# JTAG_Configuration.net
KiCad netlist of a schematic drawn in Altium Designer
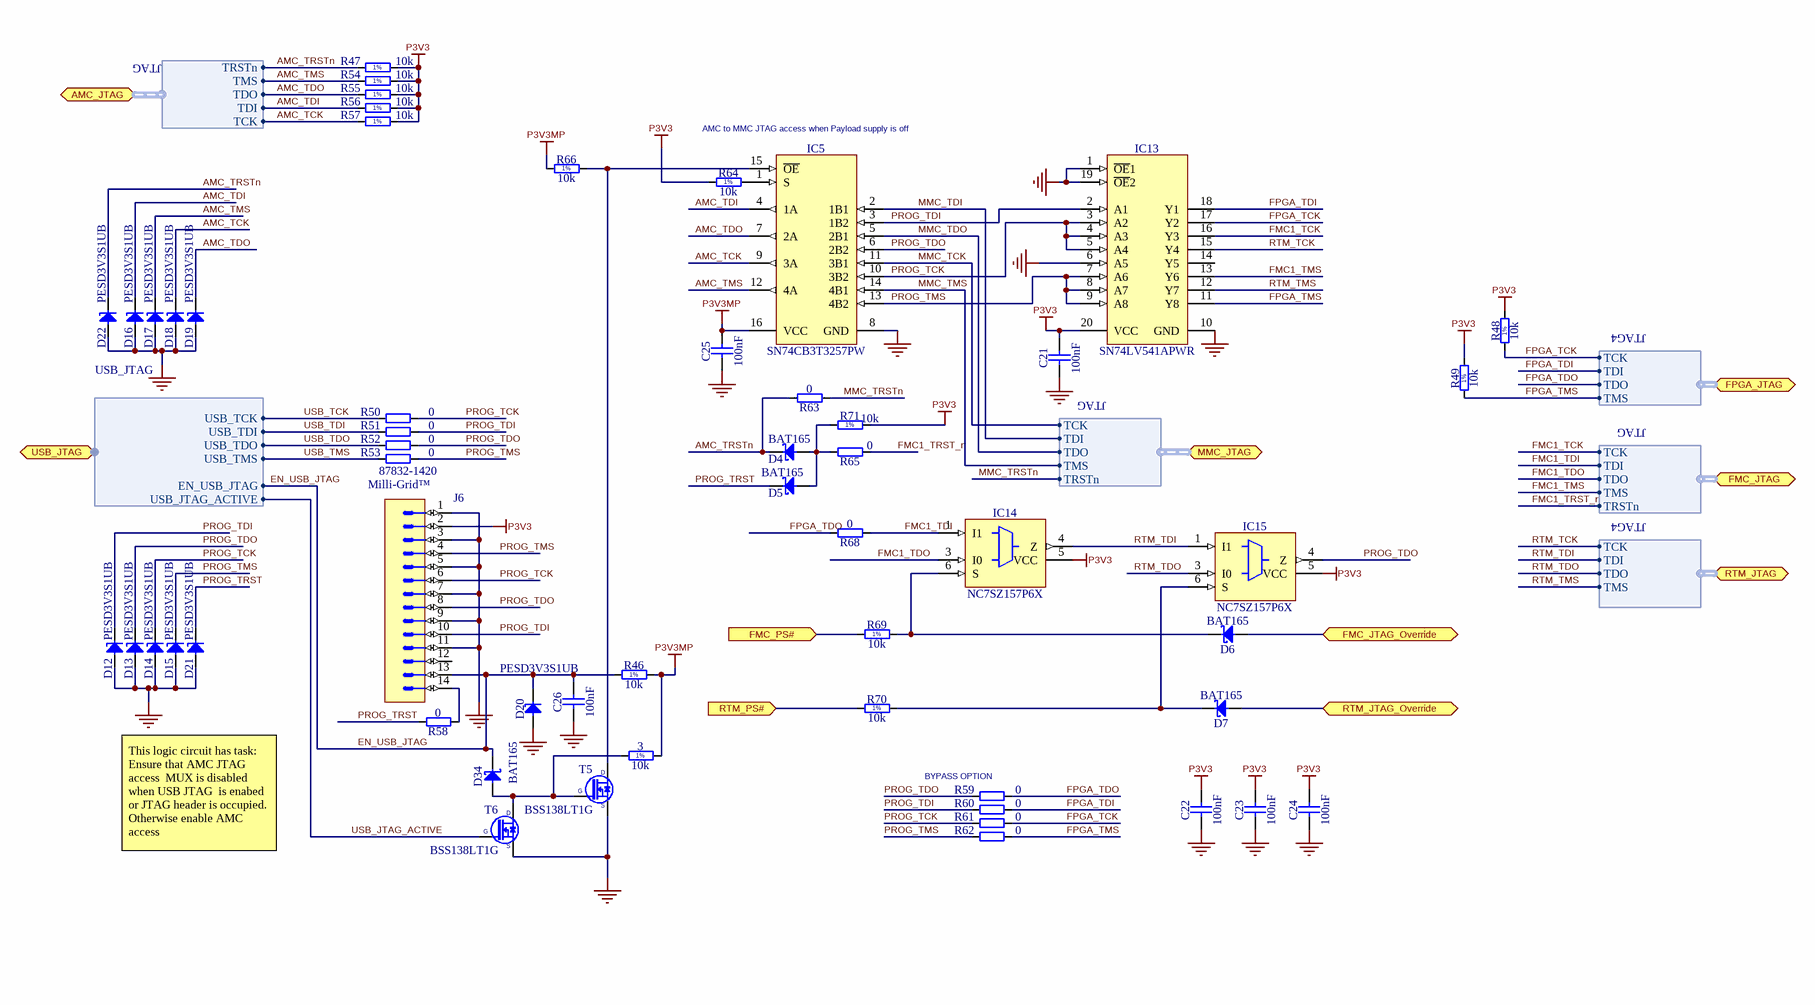
[diagram p0: JTAG_Configuration.SchDoc]

(export (version "E")
  (design (tool "Eeschema 10.0.6"))
  (components
    (comp (ref "3")
      (value "10k")
      (footprint "RESC1005X40N")
      (description "Resistor - 1%")
      (fields
        (field (name "MANUFACTURER PART NUMBER") "R0402_10K_1%_0.0625W_100PPM")
        (field (name "MANUFACTURER") "GENERIC")
        (field (name "AUTHOR") "CERN DEM JLC")
      )
      (libsource (lib "Resistors") (part "Resistor - 1%"))
    )
    (comp (ref "C21")
      (value "100nF")
      (footprint "CAPC0603X33N")
      (description "Non-polarised capacitor")
      (fields
        (field (name "MANUFACTURER PART NUMBER") "CC0201_100NF_6.3V_10%_X5R")
        (field (name "MANUFACTURER") "GENERIC")
        (field (name "AUTHOR") "CERN DEM JLC")
      )
      (libsource (lib "Capacitors") (part "Capacitor - non polarized"))
    )
    (comp (ref "C22")
      (value "100nF")
      (footprint "CAPC0603X33N")
      (description "Non-polarised capacitor")
      (fields
        (field (name "MANUFACTURER PART NUMBER") "CC0201_100NF_6.3V_10%_X5R")
        (field (name "MANUFACTURER") "GENERIC")
        (field (name "AUTHOR") "CERN DEM JLC")
      )
      (libsource (lib "Capacitors") (part "Capacitor - non polarized"))
    )
    (comp (ref "C23")
      (value "100nF")
      (footprint "CAPC0603X33N")
      (description "Non-polarised capacitor")
      (fields
        (field (name "MANUFACTURER PART NUMBER") "CC0201_100NF_6.3V_10%_X5R")
        (field (name "MANUFACTURER") "GENERIC")
        (field (name "AUTHOR") "CERN DEM JLC")
      )
      (libsource (lib "Capacitors") (part "Capacitor - non polarized"))
    )
    (comp (ref "C24")
      (value "100nF")
      (footprint "CAPC0603X33N")
      (description "Non-polarised capacitor")
      (fields
        (field (name "MANUFACTURER PART NUMBER") "CC0201_100NF_6.3V_10%_X5R")
        (field (name "MANUFACTURER") "GENERIC")
        (field (name "AUTHOR") "CERN DEM JLC")
      )
      (libsource (lib "Capacitors") (part "Capacitor - non polarized"))
    )
    (comp (ref "C25")
      (value "100nF")
      (footprint "CAPC0603X33N")
      (description "Non-polarised capacitor")
      (fields
        (field (name "MANUFACTURER PART NUMBER") "CC0201_100NF_6.3V_10%_X5R")
        (field (name "MANUFACTURER") "GENERIC")
        (field (name "AUTHOR") "CERN DEM JLC")
      )
      (libsource (lib "Capacitors") (part "Capacitor - non polarized"))
    )
    (comp (ref "C26")
      (value "100nF")
      (footprint "CAPC0603X33N")
      (description "Non-polarised capacitor")
      (fields
        (field (name "MANUFACTURER PART NUMBER") "CC0201_100NF_6.3V_10%_X5R")
        (field (name "MANUFACTURER") "GENERIC")
        (field (name "AUTHOR") "CERN DEM JLC")
      )
      (libsource (lib "Capacitors") (part "Capacitor - non polarized"))
    )
    (comp (ref "D4")
      (value "BAT165")
      (footprint "SOD2512X110N")
      (description "Schottky Diode")
      (fields
        (field (name "MANUFACTURER") "INFINEON")
        (field (name "VOLTAGE") "40V")
        (field (name "AUTHOR") "CERN DEM JLC")
      )
      (libsource (lib "ICs And Semiconductors") (part "Diode Schottky"))
    )
    (comp (ref "D5")
      (value "BAT165")
      (footprint "SOD2512X110N")
      (description "Schottky Diode")
      (fields
        (field (name "MANUFACTURER") "INFINEON")
        (field (name "VOLTAGE") "40V")
        (field (name "AUTHOR") "CERN DEM JLC")
      )
      (libsource (lib "ICs And Semiconductors") (part "Diode Schottky"))
    )
    (comp (ref "D6")
      (value "BAT165")
      (footprint "SOD2512X110N")
      (description "Schottky Diode")
      (fields
        (field (name "MANUFACTURER") "INFINEON")
        (field (name "VOLTAGE") "40V")
        (field (name "AUTHOR") "CERN DEM JLC")
      )
      (libsource (lib "ICs And Semiconductors") (part "Diode Schottky"))
    )
    (comp (ref "D7")
      (value "BAT165")
      (footprint "SOD2512X110N")
      (description "Schottky Diode")
      (fields
        (field (name "MANUFACTURER") "INFINEON")
        (field (name "VOLTAGE") "40V")
        (field (name "AUTHOR") "CERN DEM JLC")
      )
      (libsource (lib "ICs And Semiconductors") (part "Diode Schottky"))
    )
    (comp (ref "D12")
      (value "PESD3V3S1UB")
      (footprint "SODFL1608X65N")
      (description "ESD protection diode")
      (fields
        (field (name "MANUFACTURER") "NXP SEMICONDUCTORS")
        (field (name "VOLTAGE") "3V3")
        (field (name "AUTHOR") "CERN DEM JLC")
      )
      (libsource (lib "ICs And Semiconductors") (part "Diode ESD"))
    )
    (comp (ref "D13")
      (value "PESD3V3S1UB")
      (footprint "SODFL1608X65N")
      (description "ESD protection diode")
      (fields
        (field (name "MANUFACTURER") "NXP SEMICONDUCTORS")
        (field (name "VOLTAGE") "3V3")
        (field (name "AUTHOR") "CERN DEM JLC")
      )
      (libsource (lib "ICs And Semiconductors") (part "Diode ESD"))
    )
    (comp (ref "D14")
      (value "PESD3V3S1UB")
      (footprint "SODFL1608X65N")
      (description "ESD protection diode")
      (fields
        (field (name "MANUFACTURER") "NXP SEMICONDUCTORS")
        (field (name "VOLTAGE") "3V3")
        (field (name "AUTHOR") "CERN DEM JLC")
      )
      (libsource (lib "ICs And Semiconductors") (part "Diode ESD"))
    )
    (comp (ref "D15")
      (value "PESD3V3S1UB")
      (footprint "SODFL1608X65N")
      (description "ESD protection diode")
      (fields
        (field (name "MANUFACTURER") "NXP SEMICONDUCTORS")
        (field (name "VOLTAGE") "3V3")
        (field (name "AUTHOR") "CERN DEM JLC")
      )
      (libsource (lib "ICs And Semiconductors") (part "Diode ESD"))
    )
    (comp (ref "D16")
      (value "PESD3V3S1UB")
      (footprint "SODFL1608X65N")
      (description "ESD protection diode")
      (fields
        (field (name "MANUFACTURER") "NXP SEMICONDUCTORS")
        (field (name "VOLTAGE") "3V3")
        (field (name "AUTHOR") "CERN DEM JLC")
      )
      (libsource (lib "ICs And Semiconductors") (part "Diode ESD"))
    )
    (comp (ref "D17")
      (value "PESD3V3S1UB")
      (footprint "SODFL1608X65N")
      (description "ESD protection diode")
      (fields
        (field (name "MANUFACTURER") "NXP SEMICONDUCTORS")
        (field (name "VOLTAGE") "3V3")
        (field (name "AUTHOR") "CERN DEM JLC")
      )
      (libsource (lib "ICs And Semiconductors") (part "Diode ESD"))
    )
    (comp (ref "D18")
      (value "PESD3V3S1UB")
      (footprint "SODFL1608X65N")
      (description "ESD protection diode")
      (fields
        (field (name "MANUFACTURER") "NXP SEMICONDUCTORS")
        (field (name "VOLTAGE") "3V3")
        (field (name "AUTHOR") "CERN DEM JLC")
      )
      (libsource (lib "ICs And Semiconductors") (part "Diode ESD"))
    )
    (comp (ref "D19")
      (value "PESD3V3S1UB")
      (footprint "SODFL1608X65N")
      (description "ESD protection diode")
      (fields
        (field (name "MANUFACTURER") "NXP SEMICONDUCTORS")
        (field (name "VOLTAGE") "3V3")
        (field (name "AUTHOR") "CERN DEM JLC")
      )
      (libsource (lib "ICs And Semiconductors") (part "Diode ESD"))
    )
    (comp (ref "D20")
      (value "PESD3V3S1UB")
      (footprint "SODFL1608X65N")
      (description "ESD protection diode")
      (fields
        (field (name "MANUFACTURER") "NXP SEMICONDUCTORS")
        (field (name "VOLTAGE") "3V3")
        (field (name "AUTHOR") "CERN DEM JLC")
      )
      (libsource (lib "ICs And Semiconductors") (part "Diode ESD"))
    )
    (comp (ref "D21")
      (value "PESD3V3S1UB")
      (footprint "SODFL1608X65N")
      (description "ESD protection diode")
      (fields
        (field (name "MANUFACTURER") "NXP SEMICONDUCTORS")
        (field (name "VOLTAGE") "3V3")
        (field (name "AUTHOR") "CERN DEM JLC")
      )
      (libsource (lib "ICs And Semiconductors") (part "Diode ESD"))
    )
    (comp (ref "D22")
      (value "PESD3V3S1UB")
      (footprint "SODFL1608X65N")
      (description "ESD protection diode")
      (fields
        (field (name "MANUFACTURER") "NXP SEMICONDUCTORS")
        (field (name "VOLTAGE") "3V3")
        (field (name "AUTHOR") "CERN DEM JLC")
      )
      (libsource (lib "ICs And Semiconductors") (part "Diode ESD"))
    )
    (comp (ref "D34")
      (value "BAT165")
      (footprint "SOD2512X110N")
      (description "Schottky Diode")
      (fields
        (field (name "MANUFACTURER") "INFINEON")
        (field (name "VOLTAGE") "40V")
        (field (name "AUTHOR") "CERN DEM JLC")
      )
      (libsource (lib "ICs And Semiconductors") (part "Diode Schottky"))
    )
    (comp (ref "IC5")
      (value "SN74CB3T3257PW")
      (footprint "SOP65P640X120-16N")
      (description "4-BIT 1-OF-2 FET Multiplexer/Demultiplexer 2.5V/3.3V Low-Voltage Bus Switch 5V Tolerant Shifter")
      (fields (field (name "MANUFACTURER") "TEXAS INSTRUMENTS") (field (name "AUTHOR") "CERN DEM JLC"))
      (libsource (lib "ICs And Semiconductors") (part "743257"))
    )
    (comp (ref "IC13")
      (value "SN74LV541APWR")
      (footprint "SOP65P640X120-20N")
      (description "Octal Buffer/Line Driver with 3-State Outputs")
      (fields (field (name "MANUFACTURER") "TEXAS INSTRUMENTS") (field (name "AUTHOR") "CERN DEM JLC"))
      (libsource (lib "ICs And Semiconductors") (part "74541"))
    )
    (comp (ref "IC14")
      (value "NC7SZ157P6X")
      (footprint "SOT65P210X110-6N")
      (description "TinyLogic® UHS 2-Input Non-Inverting Multiplexer")
      (fields (field (name "MANUFACTURER") "FAIRCHILD SEMICONDUCTOR") (field (name "AUTHOR") "CERN DEM JLC"))
      (libsource (lib "ICs And Semiconductors") (part "NC7SZ157"))
    )
    (comp (ref "IC15")
      (value "NC7SZ157P6X")
      (footprint "SOT65P210X110-6N")
      (description "TinyLogic® UHS 2-Input Non-Inverting Multiplexer")
      (fields (field (name "MANUFACTURER") "FAIRCHILD SEMICONDUCTOR") (field (name "AUTHOR") "CERN DEM JLC"))
      (libsource (lib "ICs And Semiconductors") (part "NC7SZ157"))
    )
    (comp (ref "J6")
      (value "Milli-Grid™")
      (footprint "MOLEX_87832-1420")
      (description "Connector 14 Male")
      (fields
        (field (name "MANUFACTURER PART NUMBER") "87832-1420")
        (field (name "MANUFACTURER") "MOLEX")
        (field (name "PART NUMBER") "MOLEX_87832-1420")
        (field (name "AUTHOR") "CERN DEM JLC")
      )
      (libsource (lib "Connectors") (part "Connector 14 Male"))
    )
    (comp (ref "R46")
      (value "10k")
      (footprint "RESC1005X40N")
      (description "Resistor - 1%")
      (fields
        (field (name "MANUFACTURER PART NUMBER") "R0402_10K_1%_0.0625W_100PPM")
        (field (name "MANUFACTURER") "GENERIC")
        (field (name "AUTHOR") "CERN DEM JLC")
      )
      (libsource (lib "Resistors") (part "Resistor - 1%"))
    )
    (comp (ref "R47")
      (value "10k")
      (footprint "RESC1005X40N")
      (description "Resistor - 1%")
      (fields
        (field (name "MANUFACTURER PART NUMBER") "R0402_10K_1%_0.0625W_100PPM")
        (field (name "MANUFACTURER") "GENERIC")
        (field (name "AUTHOR") "CERN DEM JLC")
      )
      (libsource (lib "Resistors") (part "Resistor - 1%"))
    )
    (comp (ref "R48")
      (value "10k")
      (footprint "RESC1005X40N")
      (description "Resistor - 1%")
      (fields
        (field (name "MANUFACTURER PART NUMBER") "R0402_10K_1%_0.0625W_100PPM")
        (field (name "MANUFACTURER") "GENERIC")
        (field (name "AUTHOR") "CERN DEM JLC")
      )
      (libsource (lib "Resistors") (part "Resistor - 1%"))
    )
    (comp (ref "R49")
      (value "10k")
      (footprint "RESC1005X40N")
      (description "Resistor - 1%")
      (fields
        (field (name "MANUFACTURER PART NUMBER") "R0402_10K_1%_0.0625W_100PPM")
        (field (name "MANUFACTURER") "GENERIC")
        (field (name "AUTHOR") "CERN DEM JLC")
      )
      (libsource (lib "Resistors") (part "Resistor - 1%"))
    )
    (comp (ref "R50")
      (value "0")
      (footprint "RESC1005X40N")
      (description "Resistor")
      (fields
        (field (name "MANUFACTURER PART NUMBER") "R0402_0R_JUMPER")
        (field (name "MANUFACTURER") "GENERIC")
        (field (name "AUTHOR") "CERN DEM JLC")
      )
      (libsource (lib "Resistors") (part "Resistor"))
    )
    (comp (ref "R51")
      (value "0")
      (footprint "RESC1005X40N")
      (description "Resistor")
      (fields
        (field (name "MANUFACTURER PART NUMBER") "R0402_0R_JUMPER")
        (field (name "MANUFACTURER") "GENERIC")
        (field (name "AUTHOR") "CERN DEM JLC")
      )
      (libsource (lib "Resistors") (part "Resistor"))
    )
    (comp (ref "R52")
      (value "0")
      (footprint "RESC1005X40N")
      (description "Resistor")
      (fields
        (field (name "MANUFACTURER PART NUMBER") "R0402_0R_JUMPER")
        (field (name "MANUFACTURER") "GENERIC")
        (field (name "AUTHOR") "CERN DEM JLC")
      )
      (libsource (lib "Resistors") (part "Resistor"))
    )
    (comp (ref "R53")
      (value "0")
      (footprint "RESC1005X40N")
      (description "Resistor")
      (fields
        (field (name "MANUFACTURER PART NUMBER") "R0402_0R_JUMPER")
        (field (name "MANUFACTURER") "GENERIC")
        (field (name "AUTHOR") "CERN DEM JLC")
      )
      (libsource (lib "Resistors") (part "Resistor"))
    )
    (comp (ref "R54")
      (value "10k")
      (footprint "RESC1005X40N")
      (description "Resistor - 1%")
      (fields
        (field (name "MANUFACTURER PART NUMBER") "R0402_10K_1%_0.0625W_100PPM")
        (field (name "MANUFACTURER") "GENERIC")
        (field (name "AUTHOR") "CERN DEM JLC")
      )
      (libsource (lib "Resistors") (part "Resistor - 1%"))
    )
    (comp (ref "R55")
      (value "10k")
      (footprint "RESC1005X40N")
      (description "Resistor - 1%")
      (fields
        (field (name "MANUFACTURER PART NUMBER") "R0402_10K_1%_0.0625W_100PPM")
        (field (name "MANUFACTURER") "GENERIC")
        (field (name "AUTHOR") "CERN DEM JLC")
      )
      (libsource (lib "Resistors") (part "Resistor - 1%"))
    )
    (comp (ref "R56")
      (value "10k")
      (footprint "RESC1005X40N")
      (description "Resistor - 1%")
      (fields
        (field (name "MANUFACTURER PART NUMBER") "R0402_10K_1%_0.0625W_100PPM")
        (field (name "MANUFACTURER") "GENERIC")
        (field (name "AUTHOR") "CERN DEM JLC")
      )
      (libsource (lib "Resistors") (part "Resistor - 1%"))
    )
    (comp (ref "R57")
      (value "10k")
      (footprint "RESC1005X40N")
      (description "Resistor - 1%")
      (fields
        (field (name "MANUFACTURER PART NUMBER") "R0402_10K_1%_0.0625W_100PPM")
        (field (name "MANUFACTURER") "GENERIC")
        (field (name "AUTHOR") "CERN DEM JLC")
      )
      (libsource (lib "Resistors") (part "Resistor - 1%"))
    )
    (comp (ref "R58")
      (value "0")
      (footprint "RESC1005X40N")
      (description "Resistor")
      (fields
        (field (name "MANUFACTURER PART NUMBER") "R0402_0R_JUMPER")
        (field (name "MANUFACTURER") "GENERIC")
        (field (name "AUTHOR") "CERN DEM JLC")
      )
      (libsource (lib "Resistors") (part "Resistor"))
    )
    (comp (ref "R59")
      (value "0")
      (footprint "RESC1005X40N")
      (description "Resistor")
      (fields
        (field (name "MANUFACTURER PART NUMBER") "R0402_0R_JUMPER")
        (field (name "MANUFACTURER") "GENERIC")
        (field (name "AUTHOR") "CERN DEM JLC")
      )
      (libsource (lib "Resistors") (part "Resistor"))
    )
    (comp (ref "R60")
      (value "0")
      (footprint "RESC1005X40N")
      (description "Resistor")
      (fields
        (field (name "MANUFACTURER PART NUMBER") "R0402_0R_JUMPER")
        (field (name "MANUFACTURER") "GENERIC")
        (field (name "AUTHOR") "CERN DEM JLC")
      )
      (libsource (lib "Resistors") (part "Resistor"))
    )
    (comp (ref "R61")
      (value "0")
      (footprint "RESC1005X40N")
      (description "Resistor")
      (fields
        (field (name "MANUFACTURER PART NUMBER") "R0402_0R_JUMPER")
        (field (name "MANUFACTURER") "GENERIC")
        (field (name "AUTHOR") "CERN DEM JLC")
      )
      (libsource (lib "Resistors") (part "Resistor"))
    )
    (comp (ref "R62")
      (value "0")
      (footprint "RESC1005X40N")
      (description "Resistor")
      (fields
        (field (name "MANUFACTURER PART NUMBER") "R0402_0R_JUMPER")
        (field (name "MANUFACTURER") "GENERIC")
        (field (name "AUTHOR") "CERN DEM JLC")
      )
      (libsource (lib "Resistors") (part "Resistor"))
    )
    (comp (ref "R63")
      (value "0")
      (footprint "RESC1005X40N")
      (description "Resistor")
      (fields
        (field (name "MANUFACTURER PART NUMBER") "R0402_0R_JUMPER")
        (field (name "MANUFACTURER") "GENERIC")
        (field (name "AUTHOR") "CERN DEM JLC")
      )
      (libsource (lib "Resistors") (part "Resistor"))
    )
    (comp (ref "R64")
      (value "10k")
      (footprint "RESC1005X40N")
      (description "Resistor - 1%")
      (fields
        (field (name "MANUFACTURER PART NUMBER") "R0402_10K_1%_0.0625W_100PPM")
        (field (name "MANUFACTURER") "GENERIC")
        (field (name "AUTHOR") "CERN DEM JLC")
      )
      (libsource (lib "Resistors") (part "Resistor - 1%"))
    )
    (comp (ref "R65")
      (value "0")
      (footprint "RESC1005X40N")
      (description "Resistor")
      (fields
        (field (name "MANUFACTURER PART NUMBER") "R0402_0R_JUMPER")
        (field (name "MANUFACTURER") "GENERIC")
        (field (name "AUTHOR") "CERN DEM JLC")
      )
      (libsource (lib "Resistors") (part "Resistor"))
    )
    (comp (ref "R66")
      (value "10k")
      (footprint "RESC1005X40N")
      (description "Resistor - 1%")
      (fields
        (field (name "MANUFACTURER PART NUMBER") "R0402_10K_1%_0.0625W_100PPM")
        (field (name "MANUFACTURER") "GENERIC")
        (field (name "AUTHOR") "CERN DEM JLC")
      )
      (libsource (lib "Resistors") (part "Resistor - 1%"))
    )
    (comp (ref "R68")
      (value "0")
      (footprint "RESC1005X40N")
      (description "Resistor")
      (fields
        (field (name "MANUFACTURER PART NUMBER") "R0402_0R_JUMPER")
        (field (name "MANUFACTURER") "GENERIC")
        (field (name "AUTHOR") "CERN DEM JLC")
      )
      (libsource (lib "Resistors") (part "Resistor"))
    )
    (comp (ref "R69")
      (value "10k")
      (footprint "RESC1005X40N")
      (description "Resistor - 1%")
      (fields
        (field (name "MANUFACTURER PART NUMBER") "R0402_10K_1%_0.0625W_100PPM")
        (field (name "MANUFACTURER") "GENERIC")
        (field (name "AUTHOR") "CERN DEM JLC")
      )
      (libsource (lib "Resistors") (part "Resistor - 1%"))
    )
    (comp (ref "R70")
      (value "10k")
      (footprint "RESC1005X40N")
      (description "Resistor - 1%")
      (fields
        (field (name "MANUFACTURER PART NUMBER") "R0402_10K_1%_0.0625W_100PPM")
        (field (name "MANUFACTURER") "GENERIC")
        (field (name "AUTHOR") "CERN DEM JLC")
      )
      (libsource (lib "Resistors") (part "Resistor - 1%"))
    )
    (comp (ref "R71")
      (value "10k")
      (footprint "RESC1005X40N")
      (description "Resistor - 1%")
      (fields
        (field (name "MANUFACTURER PART NUMBER") "R0402_10K_1%_0.0625W_100PPM")
        (field (name "MANUFACTURER") "GENERIC")
        (field (name "AUTHOR") "CERN DEM JLC")
      )
      (libsource (lib "Resistors") (part "Resistor - 1%"))
    )
    (comp (ref "T5")
      (value "BSS138LT1G")
      (footprint "SOT95P240X110-3N")
      (description "N-CHANNEL MOSFET WITH DIODE")
      (fields (field (name "MANUFACTURER") "ON SEMICONDUCTOR") (field (name "AUTHOR") "CERN DEM JLC"))
      (libsource (lib "ICs And Semiconductors") (part "N-MOSFET-D 1G 2S 3D"))
    )
    (comp (ref "T6")
      (value "BSS138LT1G")
      (footprint "SOT95P240X110-3N")
      (description "N-CHANNEL MOSFET WITH DIODE")
      (fields (field (name "MANUFACTURER") "ON SEMICONDUCTOR") (field (name "AUTHOR") "CERN DEM JLC"))
      (libsource (lib "ICs And Semiconductors") (part "N-MOSFET-D 1G 2S 3D"))
    )
  )
  (nets
    (net (code "4") (name "/AMC_TCK") (class "Default")
      (node (ref "D18") (pin "1") (pinfunction "C_1") (pintype "passive"))
      (node (ref "IC5") (pin "9") (pinfunction "3A_9") (pintype "output"))
      (node (ref "R57") (pin "2") (pinfunction "2_2") (pintype "passive"))
    )
    (net (code "5") (name "/AMC_TDI") (class "Default")
      (node (ref "D16") (pin "1") (pinfunction "C_1") (pintype "passive"))
      (node (ref "IC5") (pin "4") (pinfunction "1A_4") (pintype "output"))
      (node (ref "R56") (pin "2") (pinfunction "2_2") (pintype "passive"))
    )
    (net (code "6") (name "/AMC_TDO") (class "Default")
      (node (ref "D19") (pin "1") (pinfunction "C_1") (pintype "passive"))
      (node (ref "IC5") (pin "7") (pinfunction "2A_7") (pintype "output"))
      (node (ref "R55") (pin "2") (pinfunction "2_2") (pintype "passive"))
    )
    (net (code "7") (name "/AMC_TMS") (class "Default")
      (node (ref "D17") (pin "1") (pinfunction "C_1") (pintype "passive"))
      (node (ref "IC5") (pin "12") (pinfunction "4A_12") (pintype "output"))
      (node (ref "R54") (pin "2") (pinfunction "2_2") (pintype "passive"))
    )
    (net (code "8") (name "/AMC_TRSTn") (class "Default")
      (node (ref "D22") (pin "1") (pinfunction "C_1") (pintype "passive"))
      (node (ref "D4") (pin "1") (pinfunction "C_1") (pintype "passive"))
      (node (ref "R47") (pin "2") (pinfunction "2_2") (pintype "passive"))
      (node (ref "R63") (pin "2") (pinfunction "2_2") (pintype "passive"))
    )
    (net (code "9") (name "/EN_USB_JTAG") (class "Default")
      (node (ref "C26") (pin "2") (pinfunction "2_2") (pintype "passive"))
      (node (ref "D20") (pin "1") (pinfunction "C_1") (pintype "passive"))
      (node (ref "D34") (pin "1") (pinfunction "C_1") (pintype "passive"))
      (node (ref "J6") (pin "13") (pinfunction "13_13") (pintype "bidirectional"))
      (node (ref "R46") (pin "1") (pinfunction "1_1") (pintype "passive"))
    )
    (net (code "10") (name "/FMC1_TCK") (class "Default")
      (node (ref "IC13") (pin "16") (pinfunction "Y3_16") (pintype "tri_state"))
    )
    (net (code "11") (name "/FMC1_TDI") (class "Default")
      (node (ref "IC14") (pin "1") (pinfunction "I1_1") (pintype "input"))
      (node (ref "R68") (pin "1") (pinfunction "1_1") (pintype "passive"))
    )
    (net (code "12") (name "/FMC1_TDO") (class "Default")
      (node (ref "IC14") (pin "3") (pinfunction "I0_3") (pintype "input"))
    )
    (net (code "13") (name "/FMC1_TMS") (class "Default")
      (node (ref "IC13") (pin "13") (pinfunction "Y6_13") (pintype "tri_state"))
    )
    (net (code "14") (name "/FMC1_TRST_n") (class "Default")
      (node (ref "R65") (pin "1") (pinfunction "1_1") (pintype "passive"))
    )
    (net (code "15") (name "/FMC_JTAG_Override") (class "Default")
      (node (ref "D6") (pin "2") (pinfunction "A_2") (pintype "passive"))
    )
    (net (code "16") (name "/FMC_PS#") (class "Default")
      (node (ref "R69") (pin "2") (pinfunction "2_2") (pintype "passive"))
    )
    (net (code "17") (name "/FPGA_TCK") (class "Default")
      (node (ref "IC13") (pin "17") (pinfunction "Y2_17") (pintype "tri_state"))
      (node (ref "R48") (pin "1") (pinfunction "1_1") (pintype "passive"))
      (node (ref "R61") (pin "1") (pinfunction "1_1") (pintype "passive"))
    )
    (net (code "18") (name "/FPGA_TDI") (class "Default")
      (node (ref "IC13") (pin "18") (pinfunction "Y1_18") (pintype "tri_state"))
      (node (ref "R60") (pin "1") (pinfunction "1_1") (pintype "passive"))
    )
    (net (code "19") (name "/FPGA_TDO") (class "Default")
      (node (ref "R59") (pin "1") (pinfunction "1_1") (pintype "passive"))
      (node (ref "R68") (pin "2") (pinfunction "2_2") (pintype "passive"))
    )
    (net (code "20") (name "/FPGA_TMS") (class "Default")
      (node (ref "IC13") (pin "11") (pinfunction "Y8_11") (pintype "tri_state"))
      (node (ref "R49") (pin "1") (pinfunction "1_1") (pintype "passive"))
      (node (ref "R62") (pin "1") (pinfunction "1_1") (pintype "passive"))
    )
    (net (code "21") (name "/MMC_TCK") (class "Default")
      (node (ref "IC5") (pin "11") (pinfunction "3B1_11") (pintype "input"))
    )
    (net (code "22") (name "/MMC_TDI") (class "Default")
      (node (ref "IC5") (pin "2") (pinfunction "1B1_2") (pintype "input"))
    )
    (net (code "23") (name "/MMC_TDO") (class "Default")
      (node (ref "IC5") (pin "5") (pinfunction "2B1_5") (pintype "input"))
    )
    (net (code "24") (name "/MMC_TMS") (class "Default")
      (node (ref "IC5") (pin "14") (pinfunction "4B1_14") (pintype "input"))
    )
    (net (code "25") (name "/MMC_TRSTn") (class "Default")
      (node (ref "R63") (pin "1") (pinfunction "1_1") (pintype "passive"))
    )
    (net (code "26") (name "/PROG_TCK") (class "Default")
      (node (ref "D14") (pin "1") (pinfunction "C_1") (pintype "passive"))
      (node (ref "IC13") (pin "3") (pinfunction "A2_3") (pintype "input"))
      (node (ref "IC13") (pin "4") (pinfunction "A3_4") (pintype "input"))
      (node (ref "IC13") (pin "5") (pinfunction "A4_5") (pintype "input"))
      (node (ref "IC5") (pin "10") (pinfunction "3B2_10") (pintype "input"))
      (node (ref "J6") (pin "6") (pinfunction "6_6") (pintype "bidirectional"))
      (node (ref "R50") (pin "1") (pinfunction "1_1") (pintype "passive"))
      (node (ref "R61") (pin "2") (pinfunction "2_2") (pintype "passive"))
    )
    (net (code "27") (name "/PROG_TDI") (class "Default")
      (node (ref "D12") (pin "1") (pinfunction "C_1") (pintype "passive"))
      (node (ref "IC13") (pin "2") (pinfunction "A1_2") (pintype "input"))
      (node (ref "IC5") (pin "3") (pinfunction "1B2_3") (pintype "input"))
      (node (ref "J6") (pin "10") (pinfunction "10_10") (pintype "bidirectional"))
      (node (ref "R51") (pin "1") (pinfunction "1_1") (pintype "passive"))
      (node (ref "R60") (pin "2") (pinfunction "2_2") (pintype "passive"))
    )
    (net (code "28") (name "/PROG_TDO") (class "Default")
      (node (ref "D13") (pin "1") (pinfunction "C_1") (pintype "passive"))
      (node (ref "IC15") (pin "4") (pinfunction "Z_4") (pintype "output"))
      (node (ref "IC5") (pin "6") (pinfunction "2B2_6") (pintype "input"))
      (node (ref "J6") (pin "8") (pinfunction "8_8") (pintype "bidirectional"))
      (node (ref "R52") (pin "1") (pinfunction "1_1") (pintype "passive"))
      (node (ref "R59") (pin "2") (pinfunction "2_2") (pintype "passive"))
    )
    (net (code "29") (name "/PROG_TMS") (class "Default")
      (node (ref "D15") (pin "1") (pinfunction "C_1") (pintype "passive"))
      (node (ref "IC13") (pin "7") (pinfunction "A6_7") (pintype "input"))
      (node (ref "IC13") (pin "8") (pinfunction "A7_8") (pintype "input"))
      (node (ref "IC13") (pin "9") (pinfunction "A8_9") (pintype "input"))
      (node (ref "IC5") (pin "13") (pinfunction "4B2_13") (pintype "input"))
      (node (ref "J6") (pin "4") (pinfunction "4_4") (pintype "bidirectional"))
      (node (ref "R53") (pin "1") (pinfunction "1_1") (pintype "passive"))
      (node (ref "R62") (pin "2") (pinfunction "2_2") (pintype "passive"))
    )
    (net (code "30") (name "/PROG_TRST") (class "Default")
      (node (ref "D21") (pin "1") (pinfunction "C_1") (pintype "passive"))
      (node (ref "D5") (pin "1") (pinfunction "C_1") (pintype "passive"))
      (node (ref "R58") (pin "2") (pinfunction "2_2") (pintype "passive"))
    )
    (net (code "31") (name "/RTM_JTAG_Override") (class "Default")
      (node (ref "D7") (pin "2") (pinfunction "A_2") (pintype "passive"))
    )
    (net (code "32") (name "/RTM_PS#") (class "Default")
      (node (ref "R70") (pin "2") (pinfunction "2_2") (pintype "passive"))
    )
    (net (code "33") (name "/RTM_TCK") (class "Default")
      (node (ref "IC13") (pin "15") (pinfunction "Y4_15") (pintype "tri_state"))
    )
    (net (code "34") (name "/RTM_TDI") (class "Default")
      (node (ref "IC14") (pin "4") (pinfunction "Z_4") (pintype "output"))
      (node (ref "IC15") (pin "1") (pinfunction "I1_1") (pintype "input"))
    )
    (net (code "35") (name "/RTM_TDO") (class "Default")
      (node (ref "IC15") (pin "3") (pinfunction "I0_3") (pintype "input"))
    )
    (net (code "36") (name "/RTM_TMS") (class "Default")
      (node (ref "IC13") (pin "12") (pinfunction "Y7_12") (pintype "tri_state"))
    )
    (net (code "37") (name "/USB_JTAG_ACTIVE") (class "Default")
      (node (ref "T6") (pin "1") (pinfunction "G_1") (pintype "passive"))
    )
    (net (code "38") (name "/USB_TCK") (class "Default")
      (node (ref "R50") (pin "2") (pinfunction "2_2") (pintype "passive"))
    )
    (net (code "39") (name "/USB_TDI") (class "Default")
      (node (ref "R51") (pin "2") (pinfunction "2_2") (pintype "passive"))
    )
    (net (code "40") (name "/USB_TDO") (class "Default")
      (node (ref "R52") (pin "2") (pinfunction "2_2") (pintype "passive"))
    )
    (net (code "41") (name "/USB_TMS") (class "Default")
      (node (ref "R53") (pin "2") (pinfunction "2_2") (pintype "passive"))
    )
    (net (code "45") (name "GND") (class "Default")
      (node (ref "C21") (pin "1") (pinfunction "1_1") (pintype "passive"))
      (node (ref "C22") (pin "1") (pinfunction "1_1") (pintype "passive"))
      (node (ref "C23") (pin "1") (pinfunction "1_1") (pintype "passive"))
      (node (ref "C24") (pin "1") (pinfunction "1_1") (pintype "passive"))
      (node (ref "C25") (pin "1") (pinfunction "1_1") (pintype "passive"))
      (node (ref "C26") (pin "1") (pinfunction "1_1") (pintype "passive"))
      (node (ref "D12") (pin "2") (pinfunction "A_2") (pintype "passive"))
      (node (ref "D13") (pin "2") (pinfunction "A_2") (pintype "passive"))
      (node (ref "D14") (pin "2") (pinfunction "A_2") (pintype "passive"))
      (node (ref "D15") (pin "2") (pinfunction "A_2") (pintype "passive"))
      (node (ref "D16") (pin "2") (pinfunction "A_2") (pintype "passive"))
      (node (ref "D17") (pin "2") (pinfunction "A_2") (pintype "passive"))
      (node (ref "D18") (pin "2") (pinfunction "A_2") (pintype "passive"))
      (node (ref "D19") (pin "2") (pinfunction "A_2") (pintype "passive"))
      (node (ref "D20") (pin "2") (pinfunction "A_2") (pintype "passive"))
      (node (ref "D21") (pin "2") (pinfunction "A_2") (pintype "passive"))
      (node (ref "D22") (pin "2") (pinfunction "A_2") (pintype "passive"))
      (node (ref "IC13") (pin "1") (pinfunction "~{OE}1_1") (pintype "input"))
      (node (ref "IC13") (pin "10") (pinfunction "GND_10") (pintype "power_in"))
      (node (ref "IC13") (pin "19") (pinfunction "~{OE}2_19") (pintype "input"))
      (node (ref "IC13") (pin "6") (pinfunction "A5_6") (pintype "input"))
      (node (ref "IC14") (pin "2") (pinfunction "GND_2") (pintype "power_in"))
      (node (ref "IC15") (pin "2") (pinfunction "GND_2") (pintype "power_in"))
      (node (ref "IC5") (pin "8") (pinfunction "GND_8") (pintype "power_in"))
      (node (ref "J6") (pin "1") (pinfunction "1_1") (pintype "bidirectional"))
      (node (ref "J6") (pin "11") (pinfunction "11_11") (pintype "bidirectional"))
      (node (ref "J6") (pin "3") (pinfunction "3_3") (pintype "bidirectional"))
      (node (ref "J6") (pin "5") (pinfunction "5_5") (pintype "bidirectional"))
      (node (ref "J6") (pin "7") (pinfunction "7_7") (pintype "bidirectional"))
      (node (ref "J6") (pin "9") (pinfunction "9_9") (pintype "bidirectional"))
      (node (ref "T5") (pin "2") (pinfunction "S_2") (pintype "passive"))
      (node (ref "T6") (pin "2") (pinfunction "S_2") (pintype "passive"))
    )
    (net (code "46") (name "Net-(D4-A)") (class "Default")
      (node (ref "D4") (pin "2") (pinfunction "A_2") (pintype "passive"))
      (node (ref "D5") (pin "2") (pinfunction "A_2") (pintype "passive"))
      (node (ref "R65") (pin "2") (pinfunction "2_2") (pintype "passive"))
      (node (ref "R71") (pin "2") (pinfunction "2_2") (pintype "passive"))
    )
    (net (code "47") (name "Net-(D6-C)") (class "Default")
      (node (ref "D6") (pin "1") (pinfunction "C_1") (pintype "passive"))
      (node (ref "IC14") (pin "6") (pinfunction "S_6") (pintype "input"))
      (node (ref "R69") (pin "1") (pinfunction "1_1") (pintype "passive"))
    )
    (net (code "48") (name "Net-(D7-C)") (class "Default")
      (node (ref "D7") (pin "1") (pinfunction "C_1") (pintype "passive"))
      (node (ref "IC15") (pin "6") (pinfunction "S_6") (pintype "input"))
      (node (ref "R70") (pin "1") (pinfunction "1_1") (pintype "passive"))
    )
    (net (code "49") (name "Net-(D34-A)") (class "Default")
      (node (ref "3") (pin "1") (pinfunction "1_1") (pintype "passive"))
      (node (ref "D34") (pin "2") (pinfunction "A_2") (pintype "passive"))
      (node (ref "T5") (pin "1") (pinfunction "G_1") (pintype "passive"))
      (node (ref "T6") (pin "3") (pinfunction "D_3") (pintype "passive"))
    )
    (net (code "50") (name "Net-(IC5-S)") (class "Default")
      (node (ref "IC5") (pin "1") (pinfunction "S_1") (pintype "input"))
      (node (ref "R64") (pin "1") (pinfunction "1_1") (pintype "passive"))
    )
    (net (code "51") (name "Net-(IC5-~{OE})") (class "Default")
      (node (ref "IC5") (pin "15") (pinfunction "~{OE}_15") (pintype "input"))
      (node (ref "R66") (pin "1") (pinfunction "1_1") (pintype "passive"))
      (node (ref "T5") (pin "3") (pinfunction "D_3") (pintype "passive"))
    )
    (net (code "52") (name "Net-(J6-Pad14)") (class "Default")
      (node (ref "J6") (pin "14") (pinfunction "14_14") (pintype "bidirectional"))
      (node (ref "R58") (pin "1") (pinfunction "1_1") (pintype "passive"))
    )
    (net (code "53") (name "P3V3") (class "Default")
      (node (ref "C21") (pin "2") (pinfunction "2_2") (pintype "passive"))
      (node (ref "C22") (pin "2") (pinfunction "2_2") (pintype "passive"))
      (node (ref "C23") (pin "2") (pinfunction "2_2") (pintype "passive"))
      (node (ref "C24") (pin "2") (pinfunction "2_2") (pintype "passive"))
      (node (ref "IC13") (pin "20") (pinfunction "VCC_20") (pintype "power_in"))
      (node (ref "IC14") (pin "5") (pinfunction "VCC_5") (pintype "power_in"))
      (node (ref "IC15") (pin "5") (pinfunction "VCC_5") (pintype "power_in"))
      (node (ref "J6") (pin "2") (pinfunction "2_2") (pintype "bidirectional"))
      (node (ref "R47") (pin "1") (pinfunction "1_1") (pintype "passive"))
      (node (ref "R48") (pin "2") (pinfunction "2_2") (pintype "passive"))
      (node (ref "R49") (pin "2") (pinfunction "2_2") (pintype "passive"))
      (node (ref "R54") (pin "1") (pinfunction "1_1") (pintype "passive"))
      (node (ref "R55") (pin "1") (pinfunction "1_1") (pintype "passive"))
      (node (ref "R56") (pin "1") (pinfunction "1_1") (pintype "passive"))
      (node (ref "R57") (pin "1") (pinfunction "1_1") (pintype "passive"))
      (node (ref "R64") (pin "2") (pinfunction "2_2") (pintype "passive"))
      (node (ref "R71") (pin "1") (pinfunction "1_1") (pintype "passive"))
    )
    (net (code "54") (name "P3V3MP") (class "Default")
      (node (ref "3") (pin "2") (pinfunction "2_2") (pintype "passive"))
      (node (ref "C25") (pin "2") (pinfunction "2_2") (pintype "passive"))
      (node (ref "IC5") (pin "16") (pinfunction "VCC_16") (pintype "power_in"))
      (node (ref "R46") (pin "2") (pinfunction "2_2") (pintype "passive"))
      (node (ref "R66") (pin "2") (pinfunction "2_2") (pintype "passive"))
    )
    (net (code "55") (name "unconnected-(IC13-Y5-Pad14)") (class "Default")
      (node (ref "IC13") (pin "14") (pinfunction "Y5_14") (pintype "tri_state"))
    )
    (net (code "56") (name "unconnected-(J6-Pad12)") (class "Default")
      (node (ref "J6") (pin "12") (pinfunction "12_12") (pintype "bidirectional"))
    )
  )
)
